# pneumatic_board2.net
KiCad netlist of a schematic drawn in EAGLE
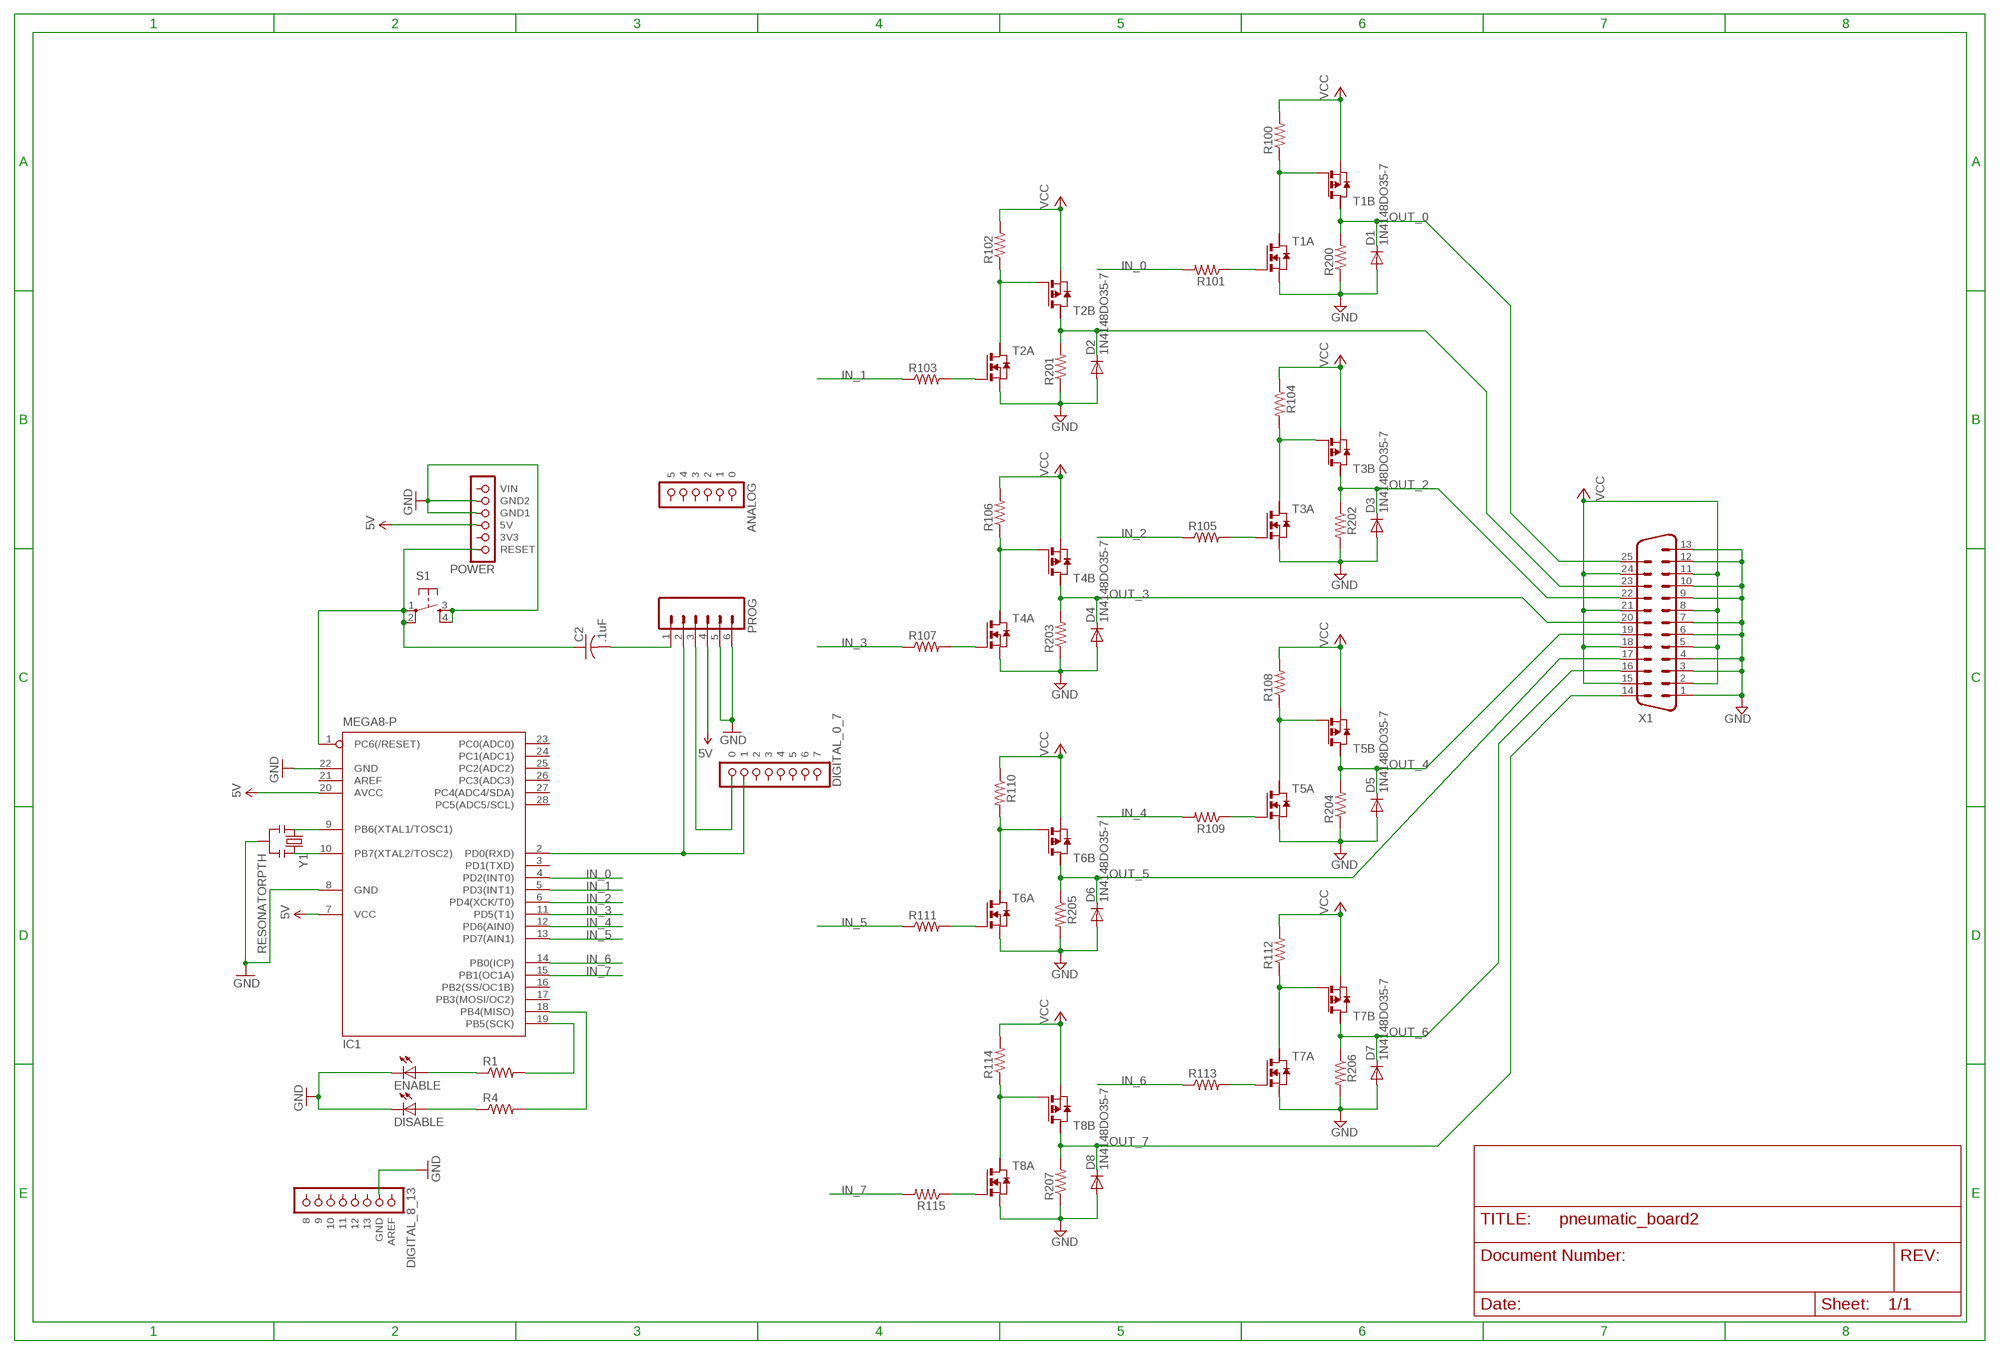
[diagram p0: schematic, sheet 1]

(export (version "E")
  (design (tool "Eeschema 10.0.6"))
  (components
    (comp (ref "C2")
      (value ".1uF")
      (footprint "eagle-import:C025-024X044")
      (libsource (lib "eagle-import") (part "C-US025-024X044"))
    )
    (comp (ref "D1")
      (value "1N4148DO35-7")
      (footprint "eagle-import:DO35-7")
      (libsource (lib "eagle-import") (part "1N4148DO35-7"))
    )
    (comp (ref "D2")
      (value "1N4148DO35-7")
      (footprint "eagle-import:DO35-7")
      (libsource (lib "eagle-import") (part "1N4148DO35-7"))
    )
    (comp (ref "D3")
      (value "1N4148DO35-7")
      (footprint "eagle-import:DO35-7")
      (libsource (lib "eagle-import") (part "1N4148DO35-7"))
    )
    (comp (ref "D4")
      (value "1N4148DO35-7")
      (footprint "eagle-import:DO35-7")
      (libsource (lib "eagle-import") (part "1N4148DO35-7"))
    )
    (comp (ref "D5")
      (value "1N4148DO35-7")
      (footprint "eagle-import:DO35-7")
      (libsource (lib "eagle-import") (part "1N4148DO35-7"))
    )
    (comp (ref "D6")
      (value "1N4148DO35-7")
      (footprint "eagle-import:DO35-7")
      (libsource (lib "eagle-import") (part "1N4148DO35-7"))
    )
    (comp (ref "D7")
      (value "1N4148DO35-7")
      (footprint "eagle-import:DO35-7")
      (libsource (lib "eagle-import") (part "1N4148DO35-7"))
    )
    (comp (ref "D8")
      (value "1N4148DO35-7")
      (footprint "eagle-import:DO35-7")
      (libsource (lib "eagle-import") (part "1N4148DO35-7"))
    )
    (comp (ref "DISABLE")
      (value "LED5MM")
      (footprint "eagle-import:LED5MM")
      (libsource (lib "eagle-import") (part "LED5MM"))
    )
    (comp (ref "ENABLE")
      (value "LED5MM")
      (footprint "eagle-import:LED5MM")
      (libsource (lib "eagle-import") (part "LED5MM"))
    )
    (comp (ref "IC1")
      (value "MEGA8-P")
      (footprint "eagle-import:DIL28-3")
      (libsource (lib "eagle-import") (part "MEGA8-P"))
    )
    (comp (ref "PROG")
      (value "M06SIP_LOCK")
      (footprint "eagle-import:1X06-SIP_LOCK")
      (libsource (lib "eagle-import") (part "M06SIP_LOCK"))
    )
    (comp (ref "R1")
      (value "RESISTORAXIAL-0.3")
      (footprint "eagle-import:AXIAL-0.3")
      (libsource (lib "eagle-import") (part "RESISTORAXIAL-0.3"))
    )
    (comp (ref "R4")
      (value "RESISTORAXIAL-0.3")
      (footprint "eagle-import:AXIAL-0.3")
      (libsource (lib "eagle-import") (part "RESISTORAXIAL-0.3"))
    )
    (comp (ref "R100")
      (value "RESISTORAXIAL-0.3")
      (footprint "eagle-import:AXIAL-0.3")
      (libsource (lib "eagle-import") (part "RESISTORAXIAL-0.3"))
    )
    (comp (ref "R101")
      (value "RESISTORAXIAL-0.3")
      (footprint "eagle-import:AXIAL-0.3")
      (libsource (lib "eagle-import") (part "RESISTORAXIAL-0.3"))
    )
    (comp (ref "R102")
      (value "RESISTORAXIAL-0.3")
      (footprint "eagle-import:AXIAL-0.3")
      (libsource (lib "eagle-import") (part "RESISTORAXIAL-0.3"))
    )
    (comp (ref "R103")
      (value "RESISTORAXIAL-0.3")
      (footprint "eagle-import:AXIAL-0.3")
      (libsource (lib "eagle-import") (part "RESISTORAXIAL-0.3"))
    )
    (comp (ref "R104")
      (value "RESISTORAXIAL-0.3")
      (footprint "eagle-import:AXIAL-0.3")
      (libsource (lib "eagle-import") (part "RESISTORAXIAL-0.3"))
    )
    (comp (ref "R105")
      (value "RESISTORAXIAL-0.3")
      (footprint "eagle-import:AXIAL-0.3")
      (libsource (lib "eagle-import") (part "RESISTORAXIAL-0.3"))
    )
    (comp (ref "R106")
      (value "RESISTORAXIAL-0.3")
      (footprint "eagle-import:AXIAL-0.3")
      (libsource (lib "eagle-import") (part "RESISTORAXIAL-0.3"))
    )
    (comp (ref "R107")
      (value "RESISTORAXIAL-0.3")
      (footprint "eagle-import:AXIAL-0.3")
      (libsource (lib "eagle-import") (part "RESISTORAXIAL-0.3"))
    )
    (comp (ref "R108")
      (value "RESISTORAXIAL-0.3")
      (footprint "eagle-import:AXIAL-0.3")
      (libsource (lib "eagle-import") (part "RESISTORAXIAL-0.3"))
    )
    (comp (ref "R109")
      (value "RESISTORAXIAL-0.3")
      (footprint "eagle-import:AXIAL-0.3")
      (libsource (lib "eagle-import") (part "RESISTORAXIAL-0.3"))
    )
    (comp (ref "R110")
      (value "RESISTORAXIAL-0.3")
      (footprint "eagle-import:AXIAL-0.3")
      (libsource (lib "eagle-import") (part "RESISTORAXIAL-0.3"))
    )
    (comp (ref "R111")
      (value "RESISTORAXIAL-0.3")
      (footprint "eagle-import:AXIAL-0.3")
      (libsource (lib "eagle-import") (part "RESISTORAXIAL-0.3"))
    )
    (comp (ref "R112")
      (value "RESISTORAXIAL-0.3")
      (footprint "eagle-import:AXIAL-0.3")
      (libsource (lib "eagle-import") (part "RESISTORAXIAL-0.3"))
    )
    (comp (ref "R113")
      (value "RESISTORAXIAL-0.3")
      (footprint "eagle-import:AXIAL-0.3")
      (libsource (lib "eagle-import") (part "RESISTORAXIAL-0.3"))
    )
    (comp (ref "R114")
      (value "RESISTORAXIAL-0.3")
      (footprint "eagle-import:AXIAL-0.3")
      (libsource (lib "eagle-import") (part "RESISTORAXIAL-0.3"))
    )
    (comp (ref "R115")
      (value "RESISTORAXIAL-0.3")
      (footprint "eagle-import:AXIAL-0.3")
      (libsource (lib "eagle-import") (part "RESISTORAXIAL-0.3"))
    )
    (comp (ref "R200")
      (value "RESISTORAXIAL-0.3")
      (footprint "eagle-import:AXIAL-0.3")
      (libsource (lib "eagle-import") (part "RESISTORAXIAL-0.3"))
    )
    (comp (ref "R201")
      (value "RESISTORAXIAL-0.3")
      (footprint "eagle-import:AXIAL-0.3")
      (libsource (lib "eagle-import") (part "RESISTORAXIAL-0.3"))
    )
    (comp (ref "R202")
      (value "RESISTORAXIAL-0.3")
      (footprint "eagle-import:AXIAL-0.3")
      (libsource (lib "eagle-import") (part "RESISTORAXIAL-0.3"))
    )
    (comp (ref "R203")
      (value "RESISTORAXIAL-0.3")
      (footprint "eagle-import:AXIAL-0.3")
      (libsource (lib "eagle-import") (part "RESISTORAXIAL-0.3"))
    )
    (comp (ref "R204")
      (value "RESISTORAXIAL-0.3")
      (footprint "eagle-import:AXIAL-0.3")
      (libsource (lib "eagle-import") (part "RESISTORAXIAL-0.3"))
    )
    (comp (ref "R205")
      (value "RESISTORAXIAL-0.3")
      (footprint "eagle-import:AXIAL-0.3")
      (libsource (lib "eagle-import") (part "RESISTORAXIAL-0.3"))
    )
    (comp (ref "R206")
      (value "RESISTORAXIAL-0.3")
      (footprint "eagle-import:AXIAL-0.3")
      (libsource (lib "eagle-import") (part "RESISTORAXIAL-0.3"))
    )
    (comp (ref "R207")
      (value "RESISTORAXIAL-0.3")
      (footprint "eagle-import:AXIAL-0.3")
      (libsource (lib "eagle-import") (part "RESISTORAXIAL-0.3"))
    )
    (comp (ref "S1")
      (value "TAC_SWITCHPTH")
      (footprint "eagle-import:TACTILE-PTH")
      (libsource (lib "eagle-import") (part "TAC_SWITCHPTH"))
    )
    (comp (ref "T1")
      (value "PN_MOSFET-SO8")
      (footprint "eagle-import:SO8")
      (libsource (lib "eagle-import") (part "PN_MOSFET-SO8"))
    )
    (comp (ref "T2")
      (value "PN_MOSFET-SO8")
      (footprint "eagle-import:SO8")
      (libsource (lib "eagle-import") (part "PN_MOSFET-SO8"))
    )
    (comp (ref "T3")
      (value "PN_MOSFET-SO8")
      (footprint "eagle-import:SO8")
      (libsource (lib "eagle-import") (part "PN_MOSFET-SO8"))
    )
    (comp (ref "T4")
      (value "PN_MOSFET-SO8")
      (footprint "eagle-import:SO8")
      (libsource (lib "eagle-import") (part "PN_MOSFET-SO8"))
    )
    (comp (ref "T5")
      (value "PN_MOSFET-SO8")
      (footprint "eagle-import:SO8")
      (libsource (lib "eagle-import") (part "PN_MOSFET-SO8"))
    )
    (comp (ref "T6")
      (value "PN_MOSFET-SO8")
      (footprint "eagle-import:SO8")
      (libsource (lib "eagle-import") (part "PN_MOSFET-SO8"))
    )
    (comp (ref "T7")
      (value "PN_MOSFET-SO8")
      (footprint "eagle-import:SO8")
      (libsource (lib "eagle-import") (part "PN_MOSFET-SO8"))
    )
    (comp (ref "T8")
      (value "PN_MOSFET-SO8")
      (footprint "eagle-import:SO8")
      (libsource (lib "eagle-import") (part "PN_MOSFET-SO8"))
    )
    (comp (ref "U$1")
      (value "POWER")
      (footprint "eagle-import:1X06")
      (libsource (lib "eagle-import") (part "POWER"))
    )
    (comp (ref "U$2")
      (value "ANALOG")
      (footprint "eagle-import:1X06")
      (libsource (lib "eagle-import") (part "ANALOG"))
    )
    (comp (ref "U$3")
      (value "DIGITAL_0_7")
      (footprint "eagle-import:1X08")
      (libsource (lib "eagle-import") (part "DIGITAL_0_7"))
    )
    (comp (ref "U$4")
      (value "DIGITAL_8_13")
      (footprint "eagle-import:1X08")
      (libsource (lib "eagle-import") (part "DIGITAL_8_13"))
    )
    (comp (ref "X1")
      (value "M25VP")
      (footprint "eagle-import:M25VP")
      (libsource (lib "eagle-import") (part "M25VP"))
    )
    (comp (ref "Y1")
      (value "RESONATORPTH")
      (footprint "eagle-import:RESONATOR-PTH")
      (libsource (lib "eagle-import") (part "RESONATORPTH"))
    )
  )
  (nets
    (net (code "1") (name "/IN_0") (class "Default")
      (node (ref "IC1") (pin "4") (pinfunction "PD2(INT0)_4") (pintype "bidirectional"))
      (node (ref "R101") (pin "P$2") (pinfunction "2_P$2") (pintype "passive"))
    )
    (net (code "2") (name "/IN_1") (class "Default")
      (node (ref "IC1") (pin "5") (pinfunction "PD3(INT1)_5") (pintype "bidirectional"))
      (node (ref "R103") (pin "P$1") (pinfunction "1_P$1") (pintype "passive"))
    )
    (net (code "3") (name "/IN_2") (class "Default")
      (node (ref "IC1") (pin "6") (pinfunction "PD4(XCK/T0)_6") (pintype "bidirectional"))
      (node (ref "R105") (pin "P$1") (pinfunction "1_P$1") (pintype "passive"))
    )
    (net (code "4") (name "/IN_3") (class "Default")
      (node (ref "IC1") (pin "11") (pinfunction "PD5(T1)_11") (pintype "bidirectional"))
      (node (ref "R107") (pin "P$1") (pinfunction "1_P$1") (pintype "passive"))
    )
    (net (code "5") (name "/IN_4") (class "Default")
      (node (ref "IC1") (pin "12") (pinfunction "PD6(AIN0)_12") (pintype "bidirectional"))
      (node (ref "R109") (pin "P$2") (pinfunction "2_P$2") (pintype "passive"))
    )
    (net (code "6") (name "/IN_5") (class "Default")
      (node (ref "IC1") (pin "13") (pinfunction "PD7(AIN1)_13") (pintype "bidirectional"))
      (node (ref "R111") (pin "P$1") (pinfunction "1_P$1") (pintype "passive"))
    )
    (net (code "7") (name "/IN_6") (class "Default")
      (node (ref "IC1") (pin "14") (pinfunction "PB0(ICP)_14") (pintype "bidirectional"))
      (node (ref "R113") (pin "P$1") (pinfunction "1_P$1") (pintype "passive"))
    )
    (net (code "8") (name "/IN_7") (class "Default")
      (node (ref "IC1") (pin "15") (pinfunction "PB1(OC1A)_15") (pintype "bidirectional"))
      (node (ref "R115") (pin "P$2") (pinfunction "2_P$2") (pintype "passive"))
    )
    (net (code "9") (name "/OUT_0") (class "Default")
      (node (ref "D1") (pin "C") (pinfunction "C_C") (pintype "passive"))
      (node (ref "R200") (pin "P$2") (pinfunction "2_P$2") (pintype "passive"))
      (node (ref "T1") (pin "5") (pinfunction "D_5") (pintype "passive"))
      (node (ref "X1") (pin "25") (pinfunction "25_25") (pintype "passive"))
    )
    (net (code "10") (name "/OUT_2") (class "Default")
      (node (ref "D3") (pin "C") (pinfunction "C_C") (pintype "passive"))
      (node (ref "R202") (pin "P$1") (pinfunction "1_P$1") (pintype "passive"))
      (node (ref "T3") (pin "5") (pinfunction "D_5") (pintype "passive"))
      (node (ref "X1") (pin "22") (pinfunction "22_22") (pintype "passive"))
    )
    (net (code "11") (name "/OUT_3") (class "Default")
      (node (ref "D4") (pin "C") (pinfunction "C_C") (pintype "passive"))
      (node (ref "R203") (pin "P$2") (pinfunction "2_P$2") (pintype "passive"))
      (node (ref "T4") (pin "5") (pinfunction "D_5") (pintype "passive"))
      (node (ref "X1") (pin "20") (pinfunction "20_20") (pintype "passive"))
    )
    (net (code "12") (name "/OUT_4") (class "Default")
      (node (ref "D5") (pin "C") (pinfunction "C_C") (pintype "passive"))
      (node (ref "R204") (pin "P$2") (pinfunction "2_P$2") (pintype "passive"))
      (node (ref "T5") (pin "5") (pinfunction "D_5") (pintype "passive"))
      (node (ref "X1") (pin "19") (pinfunction "19_19") (pintype "passive"))
    )
    (net (code "13") (name "/OUT_5") (class "Default")
      (node (ref "D6") (pin "C") (pinfunction "C_C") (pintype "passive"))
      (node (ref "R205") (pin "P$1") (pinfunction "1_P$1") (pintype "passive"))
      (node (ref "T6") (pin "5") (pinfunction "D_5") (pintype "passive"))
      (node (ref "X1") (pin "17") (pinfunction "17_17") (pintype "passive"))
    )
    (net (code "14") (name "/OUT_6") (class "Default")
      (node (ref "D7") (pin "C") (pinfunction "C_C") (pintype "passive"))
      (node (ref "R206") (pin "P$1") (pinfunction "1_P$1") (pintype "passive"))
      (node (ref "T7") (pin "5") (pinfunction "D_5") (pintype "passive"))
      (node (ref "X1") (pin "16") (pinfunction "16_16") (pintype "passive"))
    )
    (net (code "15") (name "/OUT_7") (class "Default")
      (node (ref "D8") (pin "C") (pinfunction "C_C") (pintype "passive"))
      (node (ref "R207") (pin "P$2") (pinfunction "2_P$2") (pintype "passive"))
      (node (ref "T8") (pin "5") (pinfunction "D_5") (pintype "passive"))
      (node (ref "X1") (pin "14") (pinfunction "14_14") (pintype "passive"))
    )
    (net (code "16") (name "5V") (class "Default")
      (node (ref "IC1") (pin "20") (pinfunction "AVCC_20") (pintype "power_in"))
      (node (ref "IC1") (pin "7") (pinfunction "VCC_7") (pintype "power_in"))
      (node (ref "PROG") (pin "4") (pinfunction "4_4") (pintype "passive"))
      (node (ref "U$1") (pin "3") (pinfunction "5V_3") (pintype "passive"))
    )
    (net (code "17") (name "GND") (class "Default")
      (node (ref "D1") (pin "A") (pinfunction "A_A") (pintype "passive"))
      (node (ref "D2") (pin "A") (pinfunction "A_A") (pintype "passive"))
      (node (ref "D3") (pin "A") (pinfunction "A_A") (pintype "passive"))
      (node (ref "D4") (pin "A") (pinfunction "A_A") (pintype "passive"))
      (node (ref "D5") (pin "A") (pinfunction "A_A") (pintype "passive"))
      (node (ref "D6") (pin "A") (pinfunction "A_A") (pintype "passive"))
      (node (ref "D7") (pin "A") (pinfunction "A_A") (pintype "passive"))
      (node (ref "D8") (pin "A") (pinfunction "A_A") (pintype "passive"))
      (node (ref "DISABLE") (pin "K") (pinfunction "C_K") (pintype "passive"))
      (node (ref "ENABLE") (pin "K") (pinfunction "C_K") (pintype "passive"))
      (node (ref "IC1") (pin "22") (pinfunction "GND_22") (pintype "power_in"))
      (node (ref "IC1") (pin "8") (pinfunction "GND_8") (pintype "power_in"))
      (node (ref "PROG") (pin "5") (pinfunction "5_5") (pintype "passive"))
      (node (ref "PROG") (pin "6") (pinfunction "6_6") (pintype "passive"))
      (node (ref "R200") (pin "P$1") (pinfunction "1_P$1") (pintype "passive"))
      (node (ref "R201") (pin "P$1") (pinfunction "1_P$1") (pintype "passive"))
      (node (ref "R202") (pin "P$2") (pinfunction "2_P$2") (pintype "passive"))
      (node (ref "R203") (pin "P$1") (pinfunction "1_P$1") (pintype "passive"))
      (node (ref "R204") (pin "P$1") (pinfunction "1_P$1") (pintype "passive"))
      (node (ref "R205") (pin "P$2") (pinfunction "2_P$2") (pintype "passive"))
      (node (ref "R206") (pin "P$2") (pinfunction "2_P$2") (pintype "passive"))
      (node (ref "R207") (pin "P$1") (pinfunction "1_P$1") (pintype "passive"))
      (node (ref "S1") (pin "3") (pinfunction "3_3") (pintype "passive"))
      (node (ref "S1") (pin "4") (pinfunction "4_4") (pintype "passive"))
      (node (ref "T1") (pin "1") (pinfunction "S_1") (pintype "passive"))
      (node (ref "T2") (pin "1") (pinfunction "S_1") (pintype "passive"))
      (node (ref "T3") (pin "1") (pinfunction "S_1") (pintype "passive"))
      (node (ref "T4") (pin "1") (pinfunction "S_1") (pintype "passive"))
      (node (ref "T5") (pin "1") (pinfunction "S_1") (pintype "passive"))
      (node (ref "T6") (pin "1") (pinfunction "S_1") (pintype "passive"))
      (node (ref "T7") (pin "1") (pinfunction "S_1") (pintype "passive"))
      (node (ref "T8") (pin "1") (pinfunction "S_1") (pintype "passive"))
      (node (ref "U$1") (pin "4") (pinfunction "GND1_4") (pintype "passive"))
      (node (ref "U$1") (pin "5") (pinfunction "GND2_5") (pintype "passive"))
      (node (ref "U$4") (pin "2") (pinfunction "GND_2") (pintype "passive"))
      (node (ref "X1") (pin "1") (pinfunction "1_1") (pintype "passive"))
      (node (ref "X1") (pin "10") (pinfunction "10_10") (pintype "passive"))
      (node (ref "X1") (pin "12") (pinfunction "12_12") (pintype "passive"))
      (node (ref "X1") (pin "13") (pinfunction "13_13") (pintype "passive"))
      (node (ref "X1") (pin "3") (pinfunction "3_3") (pintype "passive"))
      (node (ref "X1") (pin "4") (pinfunction "4_4") (pintype "passive"))
      (node (ref "X1") (pin "6") (pinfunction "6_6") (pintype "passive"))
      (node (ref "X1") (pin "7") (pinfunction "7_7") (pintype "passive"))
      (node (ref "X1") (pin "9") (pinfunction "9_9") (pintype "passive"))
      (node (ref "Y1") (pin "2") (pinfunction "2_2") (pintype "passive"))
    )
    (net (code "18") (name "Net-(C2-Pad2)") (class "Default")
      (node (ref "C2") (pin "2") (pinfunction "2_2") (pintype "passive"))
      (node (ref "PROG") (pin "1") (pinfunction "1_1") (pintype "passive"))
    )
    (net (code "19") (name "Net-(IC1-PB4(MISO))") (class "Default")
      (node (ref "IC1") (pin "18") (pinfunction "PB4(MISO)_18") (pintype "bidirectional"))
      (node (ref "R4") (pin "P$2") (pinfunction "2_P$2") (pintype "passive"))
    )
    (net (code "20") (name "Net-(IC1-PB5(SCK))") (class "Default")
      (node (ref "IC1") (pin "19") (pinfunction "PB5(SCK)_19") (pintype "bidirectional"))
      (node (ref "R1") (pin "P$2") (pinfunction "2_P$2") (pintype "passive"))
    )
    (net (code "21") (name "Net-(IC1-PB6(XTAL1{slash}TOSC1))") (class "Default")
      (node (ref "IC1") (pin "9") (pinfunction "PB6(XTAL1/TOSC1)_9") (pintype "bidirectional"))
      (node (ref "Y1") (pin "1") (pinfunction "1_1") (pintype "passive"))
    )
    (net (code "22") (name "Net-(IC1-PB7(XTAL2{slash}TOSC2))") (class "Default")
      (node (ref "IC1") (pin "10") (pinfunction "PB7(XTAL2/TOSC2)_10") (pintype "bidirectional"))
      (node (ref "Y1") (pin "3") (pinfunction "3_3") (pintype "passive"))
    )
    (net (code "23") (name "Net-(IC1-PC6({slash}RESET))") (class "Default")
      (node (ref "C2") (pin "1") (pinfunction "1_1") (pintype "passive"))
      (node (ref "IC1") (pin "1") (pinfunction "PC6(/RESET)_1") (pintype "bidirectional"))
      (node (ref "S1") (pin "1") (pinfunction "1_1") (pintype "passive"))
      (node (ref "S1") (pin "2") (pinfunction "2_2") (pintype "passive"))
      (node (ref "U$1") (pin "1") (pinfunction "RESET_1") (pintype "passive"))
    )
    (net (code "24") (name "Net-(IC1-PD0(RXD))") (class "Default")
      (node (ref "IC1") (pin "2") (pinfunction "PD0(RXD)_2") (pintype "bidirectional"))
      (node (ref "PROG") (pin "2") (pinfunction "2_2") (pintype "passive"))
      (node (ref "U$3") (pin "7") (pinfunction "1_7") (pintype "passive"))
    )
    (net (code "25") (name "Net-(R1-1)") (class "Default")
      (node (ref "ENABLE") (pin "A") (pinfunction "A_A") (pintype "passive"))
      (node (ref "R1") (pin "P$1") (pinfunction "1_P$1") (pintype "passive"))
    )
    (net (code "26") (name "Net-(R4-1)") (class "Default")
      (node (ref "DISABLE") (pin "A") (pinfunction "A_A") (pintype "passive"))
      (node (ref "R4") (pin "P$1") (pinfunction "1_P$1") (pintype "passive"))
    )
    (net (code "27") (name "Net-(R100-1)") (class "Default")
      (node (ref "R100") (pin "P$1") (pinfunction "1_P$1") (pintype "passive"))
      (node (ref "T1") (pin "4") (pinfunction "G_4") (pintype "passive"))
      (node (ref "T1") (pin "7") (pinfunction "D_7") (pintype "passive"))
    )
    (net (code "28") (name "Net-(R101-1)") (class "Default")
      (node (ref "R101") (pin "P$1") (pinfunction "1_P$1") (pintype "passive"))
      (node (ref "T1") (pin "2") (pinfunction "G_2") (pintype "passive"))
    )
    (net (code "29") (name "Net-(R102-1)") (class "Default")
      (node (ref "R102") (pin "P$1") (pinfunction "1_P$1") (pintype "passive"))
      (node (ref "T2") (pin "4") (pinfunction "G_4") (pintype "passive"))
      (node (ref "T2") (pin "7") (pinfunction "D_7") (pintype "passive"))
    )
    (net (code "30") (name "Net-(R103-2)") (class "Default")
      (node (ref "R103") (pin "P$2") (pinfunction "2_P$2") (pintype "passive"))
      (node (ref "T2") (pin "2") (pinfunction "G_2") (pintype "passive"))
    )
    (net (code "31") (name "Net-(R104-2)") (class "Default")
      (node (ref "R104") (pin "P$2") (pinfunction "2_P$2") (pintype "passive"))
      (node (ref "T3") (pin "4") (pinfunction "G_4") (pintype "passive"))
      (node (ref "T3") (pin "7") (pinfunction "D_7") (pintype "passive"))
    )
    (net (code "32") (name "Net-(R105-2)") (class "Default")
      (node (ref "R105") (pin "P$2") (pinfunction "2_P$2") (pintype "passive"))
      (node (ref "T3") (pin "2") (pinfunction "G_2") (pintype "passive"))
    )
    (net (code "33") (name "Net-(R106-1)") (class "Default")
      (node (ref "R106") (pin "P$1") (pinfunction "1_P$1") (pintype "passive"))
      (node (ref "T4") (pin "4") (pinfunction "G_4") (pintype "passive"))
      (node (ref "T4") (pin "7") (pinfunction "D_7") (pintype "passive"))
    )
    (net (code "34") (name "Net-(R107-2)") (class "Default")
      (node (ref "R107") (pin "P$2") (pinfunction "2_P$2") (pintype "passive"))
      (node (ref "T4") (pin "2") (pinfunction "G_2") (pintype "passive"))
    )
    (net (code "35") (name "Net-(R108-1)") (class "Default")
      (node (ref "R108") (pin "P$1") (pinfunction "1_P$1") (pintype "passive"))
      (node (ref "T5") (pin "4") (pinfunction "G_4") (pintype "passive"))
      (node (ref "T5") (pin "7") (pinfunction "D_7") (pintype "passive"))
    )
    (net (code "36") (name "Net-(R109-1)") (class "Default")
      (node (ref "R109") (pin "P$1") (pinfunction "1_P$1") (pintype "passive"))
      (node (ref "T5") (pin "2") (pinfunction "G_2") (pintype "passive"))
    )
    (net (code "37") (name "Net-(R110-2)") (class "Default")
      (node (ref "R110") (pin "P$2") (pinfunction "2_P$2") (pintype "passive"))
      (node (ref "T6") (pin "4") (pinfunction "G_4") (pintype "passive"))
      (node (ref "T6") (pin "7") (pinfunction "D_7") (pintype "passive"))
    )
    (net (code "38") (name "Net-(R111-2)") (class "Default")
      (node (ref "R111") (pin "P$2") (pinfunction "2_P$2") (pintype "passive"))
      (node (ref "T6") (pin "2") (pinfunction "G_2") (pintype "passive"))
    )
    (net (code "39") (name "Net-(R112-1)") (class "Default")
      (node (ref "R112") (pin "P$1") (pinfunction "1_P$1") (pintype "passive"))
      (node (ref "T7") (pin "4") (pinfunction "G_4") (pintype "passive"))
      (node (ref "T7") (pin "7") (pinfunction "D_7") (pintype "passive"))
    )
    (net (code "40") (name "Net-(R113-2)") (class "Default")
      (node (ref "R113") (pin "P$2") (pinfunction "2_P$2") (pintype "passive"))
      (node (ref "T7") (pin "2") (pinfunction "G_2") (pintype "passive"))
    )
    (net (code "41") (name "Net-(R114-1)") (class "Default")
      (node (ref "R114") (pin "P$1") (pinfunction "1_P$1") (pintype "passive"))
      (node (ref "T8") (pin "4") (pinfunction "G_4") (pintype "passive"))
      (node (ref "T8") (pin "7") (pinfunction "D_7") (pintype "passive"))
    )
    (net (code "42") (name "Net-(R115-1)") (class "Default")
      (node (ref "R115") (pin "P$1") (pinfunction "1_P$1") (pintype "passive"))
      (node (ref "T8") (pin "2") (pinfunction "G_2") (pintype "passive"))
    )
    (net (code "43") (name "Net-(R201-2)") (class "Default")
      (node (ref "D2") (pin "C") (pinfunction "C_C") (pintype "passive"))
      (node (ref "R201") (pin "P$2") (pinfunction "2_P$2") (pintype "passive"))
      (node (ref "T2") (pin "5") (pinfunction "D_5") (pintype "passive"))
      (node (ref "X1") (pin "23") (pinfunction "23_23") (pintype "passive"))
    )
    (net (code "44") (name "Net-(U$3-0)") (class "Default")
      (node (ref "PROG") (pin "3") (pinfunction "3_3") (pintype "passive"))
      (node (ref "U$3") (pin "8") (pinfunction "0_8") (pintype "passive"))
    )
    (net (code "45") (name "VCC") (class "Default")
      (node (ref "R100") (pin "P$2") (pinfunction "2_P$2") (pintype "passive"))
      (node (ref "R102") (pin "P$2") (pinfunction "2_P$2") (pintype "passive"))
      (node (ref "R104") (pin "P$1") (pinfunction "1_P$1") (pintype "passive"))
      (node (ref "R106") (pin "P$2") (pinfunction "2_P$2") (pintype "passive"))
      (node (ref "R108") (pin "P$2") (pinfunction "2_P$2") (pintype "passive"))
      (node (ref "R110") (pin "P$1") (pinfunction "1_P$1") (pintype "passive"))
      (node (ref "R112") (pin "P$2") (pinfunction "2_P$2") (pintype "passive"))
      (node (ref "R114") (pin "P$2") (pinfunction "2_P$2") (pintype "passive"))
      (node (ref "T1") (pin "3") (pinfunction "S_3") (pintype "passive"))
      (node (ref "T2") (pin "3") (pinfunction "S_3") (pintype "passive"))
      (node (ref "T3") (pin "3") (pinfunction "S_3") (pintype "passive"))
      (node (ref "T4") (pin "3") (pinfunction "S_3") (pintype "passive"))
      (node (ref "T5") (pin "3") (pinfunction "S_3") (pintype "passive"))
      (node (ref "T6") (pin "3") (pinfunction "S_3") (pintype "passive"))
      (node (ref "T7") (pin "3") (pinfunction "S_3") (pintype "passive"))
      (node (ref "T8") (pin "3") (pinfunction "S_3") (pintype "passive"))
      (node (ref "X1") (pin "11") (pinfunction "11_11") (pintype "passive"))
      (node (ref "X1") (pin "15") (pinfunction "15_15") (pintype "passive"))
      (node (ref "X1") (pin "18") (pinfunction "18_18") (pintype "passive"))
      (node (ref "X1") (pin "2") (pinfunction "2_2") (pintype "passive"))
      (node (ref "X1") (pin "21") (pinfunction "21_21") (pintype "passive"))
      (node (ref "X1") (pin "24") (pinfunction "24_24") (pintype "passive"))
      (node (ref "X1") (pin "5") (pinfunction "5_5") (pintype "passive"))
      (node (ref "X1") (pin "8") (pinfunction "8_8") (pintype "passive"))
    )
    (net (code "46") (name "unconnected-(IC1-AREF-Pad21)") (class "Default")
      (node (ref "IC1") (pin "21") (pinfunction "AREF_21") (pintype "passive"))
    )
    (net (code "47") (name "unconnected-(IC1-PB2(SS{slash}OC1B)-Pad16)") (class "Default")
      (node (ref "IC1") (pin "16") (pinfunction "PB2(SS/OC1B)_16") (pintype "bidirectional"))
    )
    (net (code "48") (name "unconnected-(IC1-PB3(MOSI{slash}OC2)-Pad17)") (class "Default")
      (node (ref "IC1") (pin "17") (pinfunction "PB3(MOSI/OC2)_17") (pintype "bidirectional"))
    )
    (net (code "49") (name "unconnected-(IC1-PC0(ADC0)-Pad23)") (class "Default")
      (node (ref "IC1") (pin "23") (pinfunction "PC0(ADC0)_23") (pintype "bidirectional"))
    )
    (net (code "50") (name "unconnected-(IC1-PC1(ADC1)-Pad24)") (class "Default")
      (node (ref "IC1") (pin "24") (pinfunction "PC1(ADC1)_24") (pintype "bidirectional"))
    )
    (net (code "51") (name "unconnected-(IC1-PC2(ADC2)-Pad25)") (class "Default")
      (node (ref "IC1") (pin "25") (pinfunction "PC2(ADC2)_25") (pintype "bidirectional"))
    )
    (net (code "52") (name "unconnected-(IC1-PC3(ADC3)-Pad26)") (class "Default")
      (node (ref "IC1") (pin "26") (pinfunction "PC3(ADC3)_26") (pintype "bidirectional"))
    )
    (net (code "53") (name "unconnected-(IC1-PC4(ADC4{slash}SDA)-Pad27)") (class "Default")
      (node (ref "IC1") (pin "27") (pinfunction "PC4(ADC4/SDA)_27") (pintype "bidirectional"))
    )
    (net (code "54") (name "unconnected-(IC1-PC5(ADC5{slash}SCL)-Pad28)") (class "Default")
      (node (ref "IC1") (pin "28") (pinfunction "PC5(ADC5/SCL)_28") (pintype "bidirectional"))
    )
    (net (code "55") (name "unconnected-(IC1-PD1(TXD)-Pad3)") (class "Default")
      (node (ref "IC1") (pin "3") (pinfunction "PD1(TXD)_3") (pintype "bidirectional"))
    )
    (net (code "56") (name "unconnected-(T1A-D2-Pad8)") (class "Default")
      (node (ref "T1") (pin "8") (pinfunction "D2_8") (pintype "passive"))
    )
    (net (code "57") (name "unconnected-(T1B-D2-Pad6)") (class "Default")
      (node (ref "T1") (pin "6") (pinfunction "D2_6") (pintype "passive"))
    )
    (net (code "58") (name "unconnected-(T2A-D2-Pad8)") (class "Default")
      (node (ref "T2") (pin "8") (pinfunction "D2_8") (pintype "passive"))
    )
    (net (code "59") (name "unconnected-(T2B-D2-Pad6)") (class "Default")
      (node (ref "T2") (pin "6") (pinfunction "D2_6") (pintype "passive"))
    )
    (net (code "60") (name "unconnected-(T3A-D2-Pad8)") (class "Default")
      (node (ref "T3") (pin "8") (pinfunction "D2_8") (pintype "passive"))
    )
    (net (code "61") (name "unconnected-(T3B-D2-Pad6)") (class "Default")
      (node (ref "T3") (pin "6") (pinfunction "D2_6") (pintype "passive"))
    )
    (net (code "62") (name "unconnected-(T4A-D2-Pad8)") (class "Default")
      (node (ref "T4") (pin "8") (pinfunction "D2_8") (pintype "passive"))
    )
    (net (code "63") (name "unconnected-(T4B-D2-Pad6)") (class "Default")
      (node (ref "T4") (pin "6") (pinfunction "D2_6") (pintype "passive"))
    )
    (net (code "64") (name "unconnected-(T5A-D2-Pad8)") (class "Default")
      (node (ref "T5") (pin "8") (pinfunction "D2_8") (pintype "passive"))
    )
    (net (code "65") (name "unconnected-(T5B-D2-Pad6)") (class "Default")
      (node (ref "T5") (pin "6") (pinfunction "D2_6") (pintype "passive"))
    )
    (net (code "66") (name "unconnected-(T6A-D2-Pad8)") (class "Default")
      (node (ref "T6") (pin "8") (pinfunction "D2_8") (pintype "passive"))
    )
    (net (code "67") (name "unconnected-(T6B-D2-Pad6)") (class "Default")
      (node (ref "T6") (pin "6") (pinfunction "D2_6") (pintype "passive"))
    )
    (net (code "68") (name "unconnected-(T7A-D2-Pad8)") (class "Default")
      (node (ref "T7") (pin "8") (pinfunction "D2_8") (pintype "passive"))
    )
    (net (code "69") (name "unconnected-(T7B-D2-Pad6)") (class "Default")
      (node (ref "T7") (pin "6") (pinfunction "D2_6") (pintype "passive"))
    )
    (net (code "70") (name "unconnected-(T8A-D2-Pad8)") (class "Default")
      (node (ref "T8") (pin "8") (pinfunction "D2_8") (pintype "passive"))
    )
    (net (code "71") (name "unconnected-(T8B-D2-Pad6)") (class "Default")
      (node (ref "T8") (pin "6") (pinfunction "D2_6") (pintype "passive"))
    )
    (net (code "72") (name "unconnected-(U$1-3V3-Pad2)") (class "Default")
      (node (ref "U$1") (pin "2") (pinfunction "3V3_2") (pintype "passive"))
    )
    (net (code "73") (name "unconnected-(U$1-VIN-Pad6)") (class "Default")
      (node (ref "U$1") (pin "6") (pinfunction "VIN_6") (pintype "passive"))
    )
    (net (code "74") (name "unconnected-(U$2-0-Pad1)") (class "Default")
      (node (ref "U$2") (pin "1") (pinfunction "0_1") (pintype "passive"))
    )
    (net (code "75") (name "unconnected-(U$2-1-Pad2)") (class "Default")
      (node (ref "U$2") (pin "2") (pinfunction "1_2") (pintype "passive"))
    )
    (net (code "76") (name "unconnected-(U$2-2-Pad3)") (class "Default")
      (node (ref "U$2") (pin "3") (pinfunction "2_3") (pintype "passive"))
    )
    (net (code "77") (name "unconnected-(U$2-3-Pad4)") (class "Default")
      (node (ref "U$2") (pin "4") (pinfunction "3_4") (pintype "passive"))
    )
    (net (code "78") (name "unconnected-(U$2-4-Pad5)") (class "Default")
      (node (ref "U$2") (pin "5") (pinfunction "4_5") (pintype "passive"))
    )
    (net (code "79") (name "unconnected-(U$2-5-Pad6)") (class "Default")
      (node (ref "U$2") (pin "6") (pinfunction "5_6") (pintype "passive"))
    )
    (net (code "80") (name "unconnected-(U$3-2-Pad6)") (class "Default")
      (node (ref "U$3") (pin "6") (pinfunction "2_6") (pintype "passive"))
    )
    (net (code "81") (name "unconnected-(U$3-3-Pad5)") (class "Default")
      (node (ref "U$3") (pin "5") (pinfunction "3_5") (pintype "passive"))
    )
    (net (code "82") (name "unconnected-(U$3-5-Pad3)") (class "Default")
      (node (ref "U$3") (pin "3") (pinfunction "5_3") (pintype "passive"))
    )
    (net (code "83") (name "unconnected-(U$3-6-Pad2)") (class "Default")
      (node (ref "U$3") (pin "2") (pinfunction "6_2") (pintype "passive"))
    )
    (net (code "84") (name "unconnected-(U$3-7-Pad1)") (class "Default")
      (node (ref "U$3") (pin "1") (pinfunction "7_1") (pintype "passive"))
    )
    (net (code "85") (name "unconnected-(U$3-Pad4)") (class "Default")
      (node (ref "U$3") (pin "4") (pinfunction "4_4") (pintype "passive"))
    )
    (net (code "86") (name "unconnected-(U$4-9-Pad7)") (class "Default")
      (node (ref "U$4") (pin "7") (pinfunction "9_7") (pintype "passive"))
    )
    (net (code "87") (name "unconnected-(U$4-10-Pad6)") (class "Default")
      (node (ref "U$4") (pin "6") (pinfunction "10_6") (pintype "passive"))
    )
    (net (code "88") (name "unconnected-(U$4-11-Pad5)") (class "Default")
      (node (ref "U$4") (pin "5") (pinfunction "11_5") (pintype "passive"))
    )
    (net (code "89") (name "unconnected-(U$4-12-Pad4)") (class "Default")
      (node (ref "U$4") (pin "4") (pinfunction "12_4") (pintype "passive"))
    )
    (net (code "90") (name "unconnected-(U$4-13-Pad3)") (class "Default")
      (node (ref "U$4") (pin "3") (pinfunction "13_3") (pintype "passive"))
    )
    (net (code "91") (name "unconnected-(U$4-AREF-Pad1)") (class "Default")
      (node (ref "U$4") (pin "1") (pinfunction "AREF_1") (pintype "passive"))
    )
    (net (code "92") (name "unconnected-(U$4-Pad8)") (class "Default")
      (node (ref "U$4") (pin "8") (pinfunction "8_8") (pintype "passive"))
    )
  )
)
